# ESP32S3.net
KiCad netlist of a schematic drawn in Altium Designer
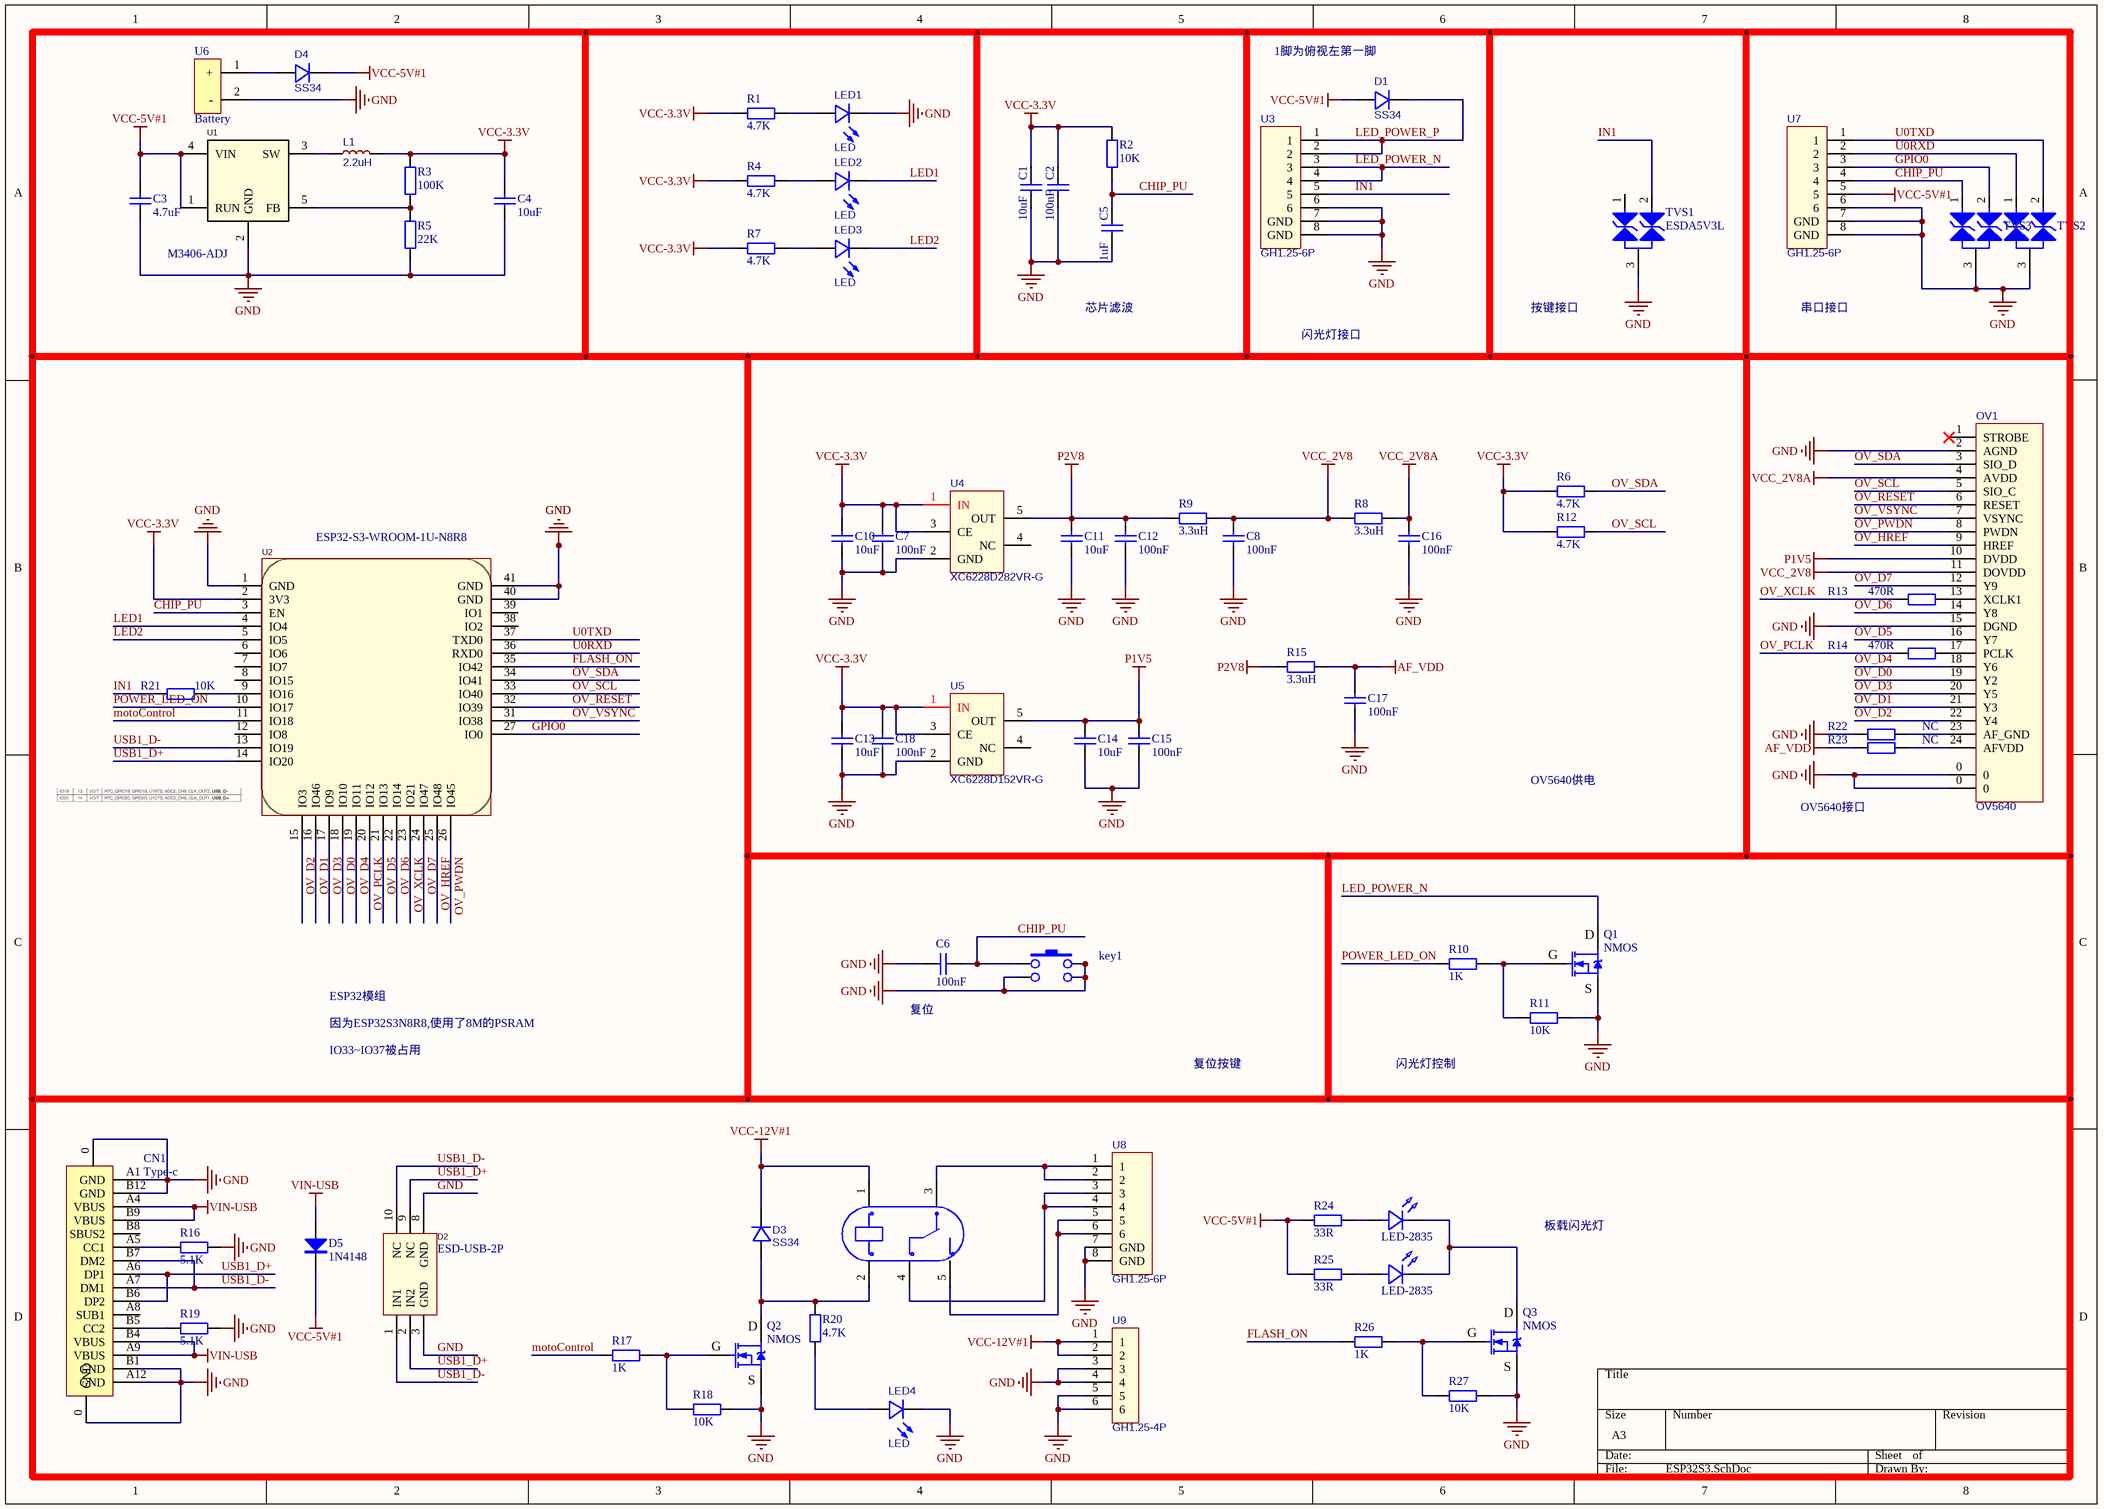
[diagram p0: ESP32S3.SchDoc]

(export (version "E")
  (design (tool "Eeschema 10.0.6"))
  (components
    (comp (ref "C1")
      (value "10uF")
      (footprint "0603-C")
      (description "贴片电容")
      (libsource (lib "封装库") (part "C"))
    )
    (comp (ref "C2")
      (value "100nF")
      (footprint "0603-C")
      (description "贴片电容")
      (libsource (lib "封装库") (part "C"))
    )
    (comp (ref "C3")
      (value "4.7uF")
      (footprint "0603-C")
      (description "贴片电容")
      (libsource (lib "封装库") (part "C"))
    )
    (comp (ref "C4")
      (value "10uF")
      (footprint "0603-C")
      (description "贴片电容")
      (libsource (lib "封装库") (part "C"))
    )
    (comp (ref "C5")
      (value "1uF")
      (footprint "0603-C")
      (description "贴片电容")
      (libsource (lib "封装库") (part "C"))
    )
    (comp (ref "C6")
      (value "100nF")
      (footprint "0603-C")
      (description "贴片电容")
      (libsource (lib "封装库") (part "C"))
    )
    (comp (ref "C7")
      (value "100nF")
      (footprint "0603-C")
      (description "贴片电容")
      (libsource (lib "封装库") (part "C"))
    )
    (comp (ref "C8")
      (value "100nF")
      (footprint "0603-C")
      (description "贴片电容")
      (libsource (lib "封装库") (part "C"))
    )
    (comp (ref "C10")
      (value "10uF")
      (footprint "0603-C")
      (description "贴片电容")
      (libsource (lib "封装库") (part "C"))
    )
    (comp (ref "C11")
      (value "10uF")
      (footprint "0603-C")
      (description "贴片电容")
      (libsource (lib "封装库") (part "C"))
    )
    (comp (ref "C12")
      (value "100nF")
      (footprint "0603-C")
      (description "贴片电容")
      (libsource (lib "封装库") (part "C"))
    )
    (comp (ref "C13")
      (value "10uF")
      (footprint "0603-C")
      (description "贴片电容")
      (libsource (lib "封装库") (part "C"))
    )
    (comp (ref "C14")
      (value "10uF")
      (footprint "0603-C")
      (description "贴片电容")
      (libsource (lib "封装库") (part "C"))
    )
    (comp (ref "C15")
      (value "100nF")
      (footprint "0603-C")
      (description "贴片电容")
      (libsource (lib "封装库") (part "C"))
    )
    (comp (ref "C16")
      (value "100nF")
      (footprint "0603-C")
      (description "贴片电容")
      (libsource (lib "封装库") (part "C"))
    )
    (comp (ref "C17")
      (value "100nF")
      (footprint "0603-C")
      (description "贴片电容")
      (libsource (lib "封装库") (part "C"))
    )
    (comp (ref "C18")
      (value "100nF")
      (footprint "0603-C")
      (description "贴片电容")
      (libsource (lib "封装库") (part "C"))
    )
    (comp (ref "CN1")
      (value "Type-c")
      (footprint "Type-c 16pin")
      (description "U262-161N-4BVC11")
      (libsource (lib "封装") (part "Type-c"))
    )
    (comp (ref "D1")
      (value "SS34")
      (footprint "SS34-SMA")
      (fields
        (field (name "BOM_SUPPLIER PART") "C118334")
        (field (name "BOM_MANUFACTURER PART") "D-G060306G1-KS2")
        (field (name "CONTRIBUTOR") "LCSC")
      )
      (libsource (lib "封装库") (part "SS34"))
    )
    (comp (ref "D2")
      (value "ESD-USB-2P")
      (footprint "SLP2510P8-2P")
      (description "RClamp0522PATCT")
      (fields (field (name "MANUFACTURER") "SEMTECH") (field (name "MANUFACTURER PART") "RClamp0524PATCT"))
      (libsource (lib "封装库") (part "ESD-USB-2P"))
    )
    (comp (ref "D3")
      (value "SS34")
      (footprint "SS34-SMA")
      (fields
        (field (name "BOM_SUPPLIER PART") "C118334")
        (field (name "BOM_MANUFACTURER PART") "D-G060306G1-KS2")
        (field (name "CONTRIBUTOR") "LCSC")
      )
      (libsource (lib "封装库") (part "SS34"))
    )
    (comp (ref "D4")
      (value "SS34")
      (footprint "SS34-SMA")
      (fields
        (field (name "BOM_SUPPLIER PART") "C118334")
        (field (name "BOM_MANUFACTURER PART") "D-G060306G1-KS2")
        (field (name "CONTRIBUTOR") "LCSC")
      )
      (libsource (lib "封装库") (part "SS34"))
    )
    (comp (ref "D5")
      (value "1N4148")
      (footprint "1N4148W")
      (description "整流二极管")
      (fields (field (name "版权归属") "源创客"))
      (libsource (lib "封装库") (part "1N4148W"))
    )
    (comp (ref "K1")
      (value "JQC-3FF/005-1ZS(551)")
      (footprint "RELAY-TH_HF3FF-XX-1ZXX-XXX")
      (fields (field (name "MANUFACTURER") "HF(宏发)"))
      (libsource (lib "封装库") (part "JQC-3FF/005-1ZS(551)"))
    )
    (comp (ref "key1") (value "KEY") (footprint "轻触开关侧按3*6*3.5") (libsource (lib "封装库") (part "轻触开关3*6*3.6")))
    (comp (ref "L1")
      (value "2.2uH")
      (footprint "电感 4.2X4.4")
      (description "L")
      (fields
        (field (name "BOM_MANUFACTURER PART") "UPZ2012D800-4R0TF")
        (field (name "BOM_SUPPLIER PART") "C145060")
        (field (name "CONTRIBUTOR") "LCSC")
      )
      (libsource (lib "封装库") (part "L"))
    )
    (comp (ref "LED1")
      (value "LED")
      (footprint "LED-0603")
      (fields
        (field (name "BOM_SUPPLIER PART") "C118334")
        (field (name "BOM_MANUFACTURER PART") "D-G060306G1-KS2")
        (field (name "CONTRIBUTOR") "LCSC")
      )
      (libsource (lib "封装库") (part "LED"))
    )
    (comp (ref "LED2")
      (value "LED")
      (footprint "LED-0603")
      (fields
        (field (name "BOM_SUPPLIER PART") "C118334")
        (field (name "BOM_MANUFACTURER PART") "D-G060306G1-KS2")
        (field (name "CONTRIBUTOR") "LCSC")
      )
      (libsource (lib "封装库") (part "LED"))
    )
    (comp (ref "LED3")
      (value "LED")
      (footprint "LED-0603")
      (fields
        (field (name "BOM_SUPPLIER PART") "C118334")
        (field (name "BOM_MANUFACTURER PART") "D-G060306G1-KS2")
        (field (name "CONTRIBUTOR") "LCSC")
      )
      (libsource (lib "封装库") (part "LED"))
    )
    (comp (ref "LED4")
      (value "LED")
      (footprint "LED-0603")
      (fields
        (field (name "BOM_SUPPLIER PART") "C118334")
        (field (name "BOM_MANUFACTURER PART") "D-G060306G1-KS2")
        (field (name "CONTRIBUTOR") "LCSC")
      )
      (libsource (lib "封装库") (part "LED"))
    )
    (comp (ref "OV1")
      (value "OV5640")
      (footprint "FPC-SMD_P0.50-24P_XJ-FGS")
      (fields (field (name "BOM_SUPPLIER PART") "C132514") (field (name "CONTRIBUTOR") "LCSC"))
      (libsource (lib "封装库") (part "OV5640"))
    )
    (comp (ref "Q1")
      (value "NMOS")
      (footprint "AO3400")
      (description "N沟道 30V/4.2A")
      (libsource (lib "封装库") (part "AO3400"))
    )
    (comp (ref "Q2")
      (value "NMOS")
      (footprint "AO3400")
      (description "N沟道 30V/4.2A")
      (libsource (lib "封装库") (part "AO3400"))
    )
    (comp (ref "Q3")
      (value "NMOS")
      (footprint "AO3400")
      (description "N沟道 30V/4.2A")
      (libsource (lib "封装库") (part "AO3400"))
    )
    (comp (ref "R1")
      (value "4.7K")
      (footprint "0603-R")
      (description "贴片电阻")
      (libsource (lib "封装库") (part "R"))
    )
    (comp (ref "R2")
      (value "10K")
      (footprint "0603-R")
      (description "贴片电阻")
      (libsource (lib "封装库") (part "R"))
    )
    (comp (ref "R3")
      (value "100K")
      (footprint "0603-R")
      (description "贴片电阻")
      (libsource (lib "封装库") (part "R"))
    )
    (comp (ref "R4")
      (value "4.7K")
      (footprint "0603-R")
      (description "贴片电阻")
      (libsource (lib "封装库") (part "R"))
    )
    (comp (ref "R5")
      (value "22K")
      (footprint "0603-R")
      (description "贴片电阻")
      (libsource (lib "封装库") (part "R"))
    )
    (comp (ref "R6")
      (value "4.7K")
      (footprint "0603-R")
      (description "贴片电阻")
      (libsource (lib "封装库") (part "R"))
    )
    (comp (ref "R7")
      (value "4.7K")
      (footprint "0603-R")
      (description "贴片电阻")
      (libsource (lib "封装库") (part "R"))
    )
    (comp (ref "R8")
      (value "3.3uH")
      (footprint "0603-R")
      (description "贴片电阻")
      (libsource (lib "封装库") (part "R"))
    )
    (comp (ref "R9")
      (value "3.3uH")
      (footprint "0603-R")
      (description "贴片电阻")
      (libsource (lib "封装库") (part "R"))
    )
    (comp (ref "R10")
      (value "1K")
      (footprint "0603-R")
      (description "贴片电阻")
      (libsource (lib "封装库") (part "R"))
    )
    (comp (ref "R11")
      (value "10K")
      (footprint "0603-R")
      (description "贴片电阻")
      (libsource (lib "封装库") (part "R"))
    )
    (comp (ref "R12")
      (value "4.7K")
      (footprint "0603-R")
      (description "贴片电阻")
      (libsource (lib "封装库") (part "R"))
    )
    (comp (ref "R13")
      (value "470R")
      (footprint "0603-R")
      (description "贴片电阻")
      (libsource (lib "封装库") (part "R"))
    )
    (comp (ref "R14")
      (value "470R")
      (footprint "0603-R")
      (description "贴片电阻")
      (libsource (lib "封装库") (part "R"))
    )
    (comp (ref "R15")
      (value "3.3uH")
      (footprint "0603-R")
      (description "贴片电阻")
      (libsource (lib "封装库") (part "R"))
    )
    (comp (ref "R16")
      (value "5.1K")
      (footprint "0603-R")
      (description "贴片电阻")
      (libsource (lib "封装库") (part "R"))
    )
    (comp (ref "R17")
      (value "1K")
      (footprint "0603-R")
      (description "贴片电阻")
      (libsource (lib "封装库") (part "R"))
    )
    (comp (ref "R18")
      (value "10K")
      (footprint "0603-R")
      (description "贴片电阻")
      (libsource (lib "封装库") (part "R"))
    )
    (comp (ref "R19")
      (value "5.1K")
      (footprint "0603-R")
      (description "贴片电阻")
      (libsource (lib "封装库") (part "R"))
    )
    (comp (ref "R20")
      (value "4.7K")
      (footprint "0603-R")
      (description "贴片电阻")
      (libsource (lib "封装库") (part "R"))
    )
    (comp (ref "R21")
      (value "10K")
      (footprint "0603-R")
      (description "贴片电阻")
      (libsource (lib "封装库") (part "R"))
    )
    (comp (ref "R22")
      (value "NC")
      (footprint "0603-R")
      (description "贴片电阻")
      (libsource (lib "封装库") (part "R"))
    )
    (comp (ref "R23")
      (value "NC")
      (footprint "0603-R")
      (description "贴片电阻")
      (libsource (lib "封装库") (part "R"))
    )
    (comp (ref "R24")
      (value "33R")
      (footprint "1206-R")
      (description "贴片电阻")
      (libsource (lib "封装库") (part "R"))
    )
    (comp (ref "R25")
      (value "33R")
      (footprint "1206-R")
      (description "贴片电阻")
      (libsource (lib "封装库") (part "R"))
    )
    (comp (ref "R26")
      (value "1K")
      (footprint "0603-R")
      (description "贴片电阻")
      (libsource (lib "封装库") (part "R"))
    )
    (comp (ref "R27")
      (value "10K")
      (footprint "0603-R")
      (description "贴片电阻")
      (libsource (lib "封装库") (part "R"))
    )
    (comp (ref "TVS1") (value "ESDA5V3L") (footprint "ESDA5V3L") (libsource (lib "封装库") (part "ESDA5V3L")))
    (comp (ref "TVS2") (value "ESDA5V3L") (footprint "ESDA5V3L") (libsource (lib "封装库") (part "ESDA5V3L")))
    (comp (ref "TVS3") (value "ESDA5V3L") (footprint "ESDA5V3L") (libsource (lib "封装库") (part "ESDA5V3L")))
    (comp (ref "U1")
      (value "M3406-ADJ")
      (footprint "M3406-ADJ")
      (fields (field (name "MANUFACTURER") "西安航天民芯"))
      (libsource (lib "封装库") (part "M3406-ADJ"))
    )
    (comp (ref "U2")
      (value "ESP32-S3-WROOM-1U-N8R8")
      (footprint "WIRELM-SMD_ESP32-S3-WROOM-1U")
      (fields
        (field (name "MANUFACTURER") "ESPRESSIF(乐鑫)")
        (field (name "MANUFACTURER PART") "ESP32-S3-WROOM-1U-N8")
      )
      (libsource (lib "封装库") (part "ESP32-S3-WROOM-1U-N8R8"))
    )
    (comp (ref "U3")
      (value "GH1.25-6P")
      (footprint "CONN-SMD_A1257WR-S-6P")
      (description "GH1.25-4PWBPZ")
      (fields (field (name "BOM_SUPPLIER PART") "C2829253") (field (name "CONTRIBUTOR") "LCSC"))
      (libsource (lib "封装库") (part "GH1.25-6P"))
    )
    (comp (ref "U4")
      (value "XC6228D282VR-G")
      (footprint "XC6228D332VR-G")
      (fields
        (field (name "BOM_MANUFACTURER PART") "XC6228D332VR-G")
        (field (name "BOM_SUPPLIER PART") "C69841")
      )
      (libsource (lib "封装库") (part "XC6228D282VR-G"))
    )
    (comp (ref "U5")
      (value "XC6228D152VR-G")
      (footprint "XC6228D332VR-G")
      (fields
        (field (name "BOM_MANUFACTURER PART") "XC6228D332VR-G")
        (field (name "BOM_SUPPLIER PART") "C69841")
      )
      (libsource (lib "封装库") (part "XC6228D282VR-G"))
    )
    (comp (ref "U6") (value "Battery") (footprint "锂电池焊盘") (libsource (lib "封装库") (part "Battery")))
    (comp (ref "U7")
      (value "GH1.25-6P")
      (footprint "CONN-SMD_A1257WR-S-6P")
      (description "GH1.25-4PWBPZ")
      (fields (field (name "BOM_SUPPLIER PART") "C2829253") (field (name "CONTRIBUTOR") "LCSC"))
      (libsource (lib "封装库") (part "GH1.25-6P"))
    )
    (comp (ref "U8")
      (value "GH1.25-6P")
      (footprint "CONN-SMD_A1257WR-S-6P")
      (description "GH1.25-4PWBPZ")
      (fields (field (name "BOM_SUPPLIER PART") "C2829253") (field (name "CONTRIBUTOR") "LCSC"))
      (libsource (lib "") (part "GH1.25-6P_1"))
    )
    (comp (ref "U9")
      (value "GH1.25-4P")
      (footprint "CONN-SMD_GH1.25-4PWBPZ")
      (description "GH1.25-4PWBPZ")
      (fields (field (name "BOM_SUPPLIER PART") "C2829253") (field (name "CONTRIBUTOR") "LCSC"))
      (libsource (lib "封装库") (part "GH1.25-4P"))
    )
    (comp (ref "U10")
      (value "LED-2835")
      (footprint "LED-SMD_L3.5-W2.8-FD-2835_WHITE")
      (fields
        (field (name "MANUFACTURER") "HONGLITRONIC(鸿利光电)")
        (field (name "MANUFACTURER PART") "A2835W3H2-D01-8D2AB5")
      )
      (libsource (lib "封装库") (part "LED-2835"))
    )
    (comp (ref "U11")
      (value "LED-2835")
      (footprint "LED-SMD_L3.5-W2.8-FD-2835_WHITE")
      (fields
        (field (name "MANUFACTURER") "HONGLITRONIC(鸿利光电)")
        (field (name "MANUFACTURER PART") "A2835W3H2-D01-8D2AB5")
      )
      (libsource (lib "封装库") (part "LED-2835"))
    )
  )
  (nets
    (net (code "1") (name "/CHIP_PU") (class "Default")
      (node (ref "C5") (pin "1") (pinfunction "1_1") (pintype "passive"))
      (node (ref "C6") (pin "1") (pinfunction "1_1") (pintype "passive"))
      (node (ref "R2") (pin "1") (pinfunction "1_1") (pintype "passive"))
      (node (ref "TVS3") (pin "1") (pinfunction "K_1") (pintype "passive"))
      (node (ref "U2") (pin "3") (pinfunction "EN_3") (pintype "passive"))
      (node (ref "U7") (pin "4") (pinfunction "4_4") (pintype "passive"))
      (node (ref "key1") (pin "1") (pinfunction "1_1") (pintype "passive"))
    )
    (net (code "2") (name "/FLASH_ON") (class "Default")
      (node (ref "R26") (pin "2") (pinfunction "2_2") (pintype "passive"))
      (node (ref "U2") (pin "35") (pinfunction "IO42_35") (pintype "passive"))
    )
    (net (code "3") (name "/GPIO0") (class "Default")
      (node (ref "TVS3") (pin "2") (pinfunction "A_2") (pintype "passive"))
      (node (ref "U2") (pin "27") (pinfunction "IO0_27") (pintype "passive"))
      (node (ref "U7") (pin "3") (pinfunction "3_3") (pintype "passive"))
    )
    (net (code "4") (name "/IN1") (class "Default")
      (node (ref "R21") (pin "2") (pinfunction "2_2") (pintype "passive"))
      (node (ref "TVS1") (pin "2") (pinfunction "A_2") (pintype "passive"))
      (node (ref "U3") (pin "5") (pinfunction "5_5") (pintype "passive"))
    )
    (net (code "5") (name "/LED1") (class "Default")
      (node (ref "LED2") (pin "1") (pinfunction "-_1") (pintype "passive"))
      (node (ref "U2") (pin "4") (pinfunction "IO4_4") (pintype "passive"))
    )
    (net (code "6") (name "/LED2") (class "Default")
      (node (ref "LED3") (pin "1") (pinfunction "-_1") (pintype "passive"))
      (node (ref "U2") (pin "5") (pinfunction "IO5_5") (pintype "passive"))
    )
    (net (code "7") (name "/LED_POWER_N") (class "Default")
      (node (ref "Q1") (pin "3") (pinfunction "D_3") (pintype "passive"))
      (node (ref "U3") (pin "3") (pinfunction "3_3") (pintype "passive"))
      (node (ref "U3") (pin "4") (pinfunction "4_4") (pintype "passive"))
    )
    (net (code "8") (name "/LED_POWER_P") (class "Default")
      (node (ref "D1") (pin "2") (pinfunction "-_2") (pintype "passive"))
      (node (ref "U3") (pin "1") (pinfunction "1_1") (pintype "passive"))
      (node (ref "U3") (pin "2") (pinfunction "2_2") (pintype "passive"))
    )
    (net (code "9") (name "/OV_D0") (class "Default")
      (node (ref "OV1") (pin "19") (pinfunction "Y2_19") (pintype "passive"))
      (node (ref "U2") (pin "18") (pinfunction "IO10_18") (pintype "passive"))
    )
    (net (code "10") (name "/OV_D1") (class "Default")
      (node (ref "OV1") (pin "21") (pinfunction "Y3_21") (pintype "passive"))
      (node (ref "U2") (pin "16") (pinfunction "IO46_16") (pintype "passive"))
    )
    (net (code "11") (name "/OV_D2") (class "Default")
      (node (ref "OV1") (pin "22") (pinfunction "Y4_22") (pintype "passive"))
      (node (ref "U2") (pin "15") (pinfunction "IO3_15") (pintype "passive"))
    )
    (net (code "12") (name "/OV_D3") (class "Default")
      (node (ref "OV1") (pin "20") (pinfunction "Y5_20") (pintype "passive"))
      (node (ref "U2") (pin "17") (pinfunction "IO9_17") (pintype "passive"))
    )
    (net (code "13") (name "/OV_D4") (class "Default")
      (node (ref "OV1") (pin "18") (pinfunction "Y6_18") (pintype "passive"))
      (node (ref "U2") (pin "19") (pinfunction "IO11_19") (pintype "passive"))
    )
    (net (code "14") (name "/OV_D5") (class "Default")
      (node (ref "OV1") (pin "16") (pinfunction "Y7_16") (pintype "passive"))
      (node (ref "U2") (pin "21") (pinfunction "IO13_21") (pintype "passive"))
    )
    (net (code "15") (name "/OV_D6") (class "Default")
      (node (ref "OV1") (pin "14") (pinfunction "Y8_14") (pintype "passive"))
      (node (ref "U2") (pin "22") (pinfunction "IO14_22") (pintype "passive"))
    )
    (net (code "16") (name "/OV_D7") (class "Default")
      (node (ref "OV1") (pin "12") (pinfunction "Y9_12") (pintype "passive"))
      (node (ref "U2") (pin "24") (pinfunction "IO47_24") (pintype "passive"))
    )
    (net (code "17") (name "/OV_HREF") (class "Default")
      (node (ref "OV1") (pin "9") (pinfunction "HREF_9") (pintype "passive"))
      (node (ref "U2") (pin "25") (pinfunction "IO48_25") (pintype "passive"))
    )
    (net (code "18") (name "/OV_PCLK") (class "Default")
      (node (ref "R14") (pin "2") (pinfunction "2_2") (pintype "passive"))
      (node (ref "U2") (pin "20") (pinfunction "IO12_20") (pintype "passive"))
    )
    (net (code "19") (name "/OV_PWDN") (class "Default")
      (node (ref "OV1") (pin "8") (pinfunction "PWDN_8") (pintype "passive"))
      (node (ref "U2") (pin "26") (pinfunction "IO45_26") (pintype "passive"))
    )
    (net (code "20") (name "/OV_RESET") (class "Default")
      (node (ref "OV1") (pin "6") (pinfunction "RESET_6") (pintype "passive"))
      (node (ref "U2") (pin "32") (pinfunction "IO39_32") (pintype "passive"))
    )
    (net (code "21") (name "/OV_SCL") (class "Default")
      (node (ref "OV1") (pin "5") (pinfunction "SIO_C_5") (pintype "passive"))
      (node (ref "R12") (pin "1") (pinfunction "1_1") (pintype "passive"))
      (node (ref "U2") (pin "33") (pinfunction "IO40_33") (pintype "passive"))
    )
    (net (code "22") (name "/OV_SDA") (class "Default")
      (node (ref "OV1") (pin "3") (pinfunction "SIO_D_3") (pintype "passive"))
      (node (ref "R6") (pin "1") (pinfunction "1_1") (pintype "passive"))
      (node (ref "U2") (pin "34") (pinfunction "IO41_34") (pintype "passive"))
    )
    (net (code "23") (name "/OV_VSYNC") (class "Default")
      (node (ref "OV1") (pin "7") (pinfunction "VSYNC_7") (pintype "passive"))
      (node (ref "U2") (pin "31") (pinfunction "IO38_31") (pintype "passive"))
    )
    (net (code "24") (name "/OV_XCLK") (class "Default")
      (node (ref "R13") (pin "2") (pinfunction "2_2") (pintype "passive"))
      (node (ref "U2") (pin "23") (pinfunction "IO21_23") (pintype "passive"))
    )
    (net (code "25") (name "/POWER_LED_ON") (class "Default")
      (node (ref "R10") (pin "2") (pinfunction "2_2") (pintype "passive"))
      (node (ref "U2") (pin "10") (pinfunction "IO17_10") (pintype "passive"))
    )
    (net (code "26") (name "/U0RXD") (class "Default")
      (node (ref "TVS2") (pin "1") (pinfunction "K_1") (pintype "passive"))
      (node (ref "U2") (pin "36") (pinfunction "RXD0_36") (pintype "passive"))
      (node (ref "U7") (pin "2") (pinfunction "2_2") (pintype "passive"))
    )
    (net (code "27") (name "/U0TXD") (class "Default")
      (node (ref "TVS2") (pin "2") (pinfunction "A_2") (pintype "passive"))
      (node (ref "U2") (pin "37") (pinfunction "TXD0_37") (pintype "passive"))
      (node (ref "U7") (pin "1") (pinfunction "1_1") (pintype "passive"))
    )
    (net (code "28") (name "/USB1_D+") (class "Default")
      (node (ref "CN1") (pin "A6") (pinfunction "DP1_A6") (pintype "passive"))
      (node (ref "CN1") (pin "B6") (pinfunction "DP2_B6") (pintype "passive"))
      (node (ref "D2") (pin "2") (pinfunction "IN2_2") (pintype "passive"))
      (node (ref "D2") (pin "9") (pinfunction "NC_9") (pintype "passive"))
      (node (ref "U2") (pin "14") (pinfunction "IO20_14") (pintype "passive"))
    )
    (net (code "29") (name "/USB1_D-") (class "Default")
      (node (ref "CN1") (pin "A7") (pinfunction "DM1_A7") (pintype "passive"))
      (node (ref "CN1") (pin "B7") (pinfunction "DM2_B7") (pintype "passive"))
      (node (ref "D2") (pin "1") (pinfunction "IN1_1") (pintype "passive"))
      (node (ref "D2") (pin "10") (pinfunction "NC_10") (pintype "passive"))
      (node (ref "U2") (pin "13") (pinfunction "IO19_13") (pintype "passive"))
    )
    (net (code "30") (name "/motoControl") (class "Default")
      (node (ref "R17") (pin "2") (pinfunction "2_2") (pintype "passive"))
      (node (ref "U2") (pin "11") (pinfunction "IO18_11") (pintype "passive"))
    )
    (net (code "31") (name "AF_VDD") (class "Default")
      (node (ref "C17") (pin "2") (pinfunction "2_2") (pintype "passive"))
      (node (ref "R15") (pin "2") (pinfunction "2_2") (pintype "passive"))
      (node (ref "R23") (pin "2") (pinfunction "2_2") (pintype "passive"))
    )
    (net (code "32") (name "GND") (class "Default")
      (node (ref "C1") (pin "1") (pinfunction "1_1") (pintype "passive"))
      (node (ref "C10") (pin "1") (pinfunction "1_1") (pintype "passive"))
      (node (ref "C11") (pin "1") (pinfunction "1_1") (pintype "passive"))
      (node (ref "C12") (pin "1") (pinfunction "1_1") (pintype "passive"))
      (node (ref "C13") (pin "1") (pinfunction "1_1") (pintype "passive"))
      (node (ref "C14") (pin "1") (pinfunction "1_1") (pintype "passive"))
      (node (ref "C15") (pin "1") (pinfunction "1_1") (pintype "passive"))
      (node (ref "C16") (pin "1") (pinfunction "1_1") (pintype "passive"))
      (node (ref "C17") (pin "1") (pinfunction "1_1") (pintype "passive"))
      (node (ref "C18") (pin "1") (pinfunction "1_1") (pintype "passive"))
      (node (ref "C2") (pin "2") (pinfunction "2_2") (pintype "passive"))
      (node (ref "C3") (pin "1") (pinfunction "1_1") (pintype "passive"))
      (node (ref "C4") (pin "1") (pinfunction "1_1") (pintype "passive"))
      (node (ref "C5") (pin "2") (pinfunction "2_2") (pintype "passive"))
      (node (ref "C6") (pin "2") (pinfunction "2_2") (pintype "passive"))
      (node (ref "C7") (pin "1") (pinfunction "1_1") (pintype "passive"))
      (node (ref "C8") (pin "1") (pinfunction "1_1") (pintype "passive"))
      (node (ref "CN1") (pin "0") (pinfunction "GND_0") (pintype "passive"))
      (node (ref "CN1") (pin "A1") (pinfunction "GND_A1") (pintype "passive"))
      (node (ref "CN1") (pin "A12") (pinfunction "GND_A12") (pintype "passive"))
      (node (ref "CN1") (pin "B1") (pinfunction "GND_B1") (pintype "passive"))
      (node (ref "CN1") (pin "B12") (pinfunction "GND_B12") (pintype "passive"))
      (node (ref "D2") (pin "3") (pinfunction "GND_3") (pintype "passive"))
      (node (ref "D2") (pin "8") (pinfunction "GND_8") (pintype "passive"))
      (node (ref "LED1") (pin "1") (pinfunction "-_1") (pintype "passive"))
      (node (ref "LED4") (pin "1") (pinfunction "-_1") (pintype "passive"))
      (node (ref "OV1") (pin "0") (pinfunction "0_0") (pintype "passive"))
      (node (ref "OV1") (pin "15") (pinfunction "DGND_15") (pintype "passive"))
      (node (ref "OV1") (pin "2") (pinfunction "AGND_2") (pintype "passive"))
      (node (ref "Q1") (pin "2") (pinfunction "S_2") (pintype "passive"))
      (node (ref "Q2") (pin "2") (pinfunction "S_2") (pintype "passive"))
      (node (ref "Q3") (pin "2") (pinfunction "S_2") (pintype "passive"))
      (node (ref "R11") (pin "1") (pinfunction "1_1") (pintype "passive"))
      (node (ref "R16") (pin "2") (pinfunction "2_2") (pintype "passive"))
      (node (ref "R18") (pin "1") (pinfunction "1_1") (pintype "passive"))
      (node (ref "R19") (pin "2") (pinfunction "2_2") (pintype "passive"))
      (node (ref "R22") (pin "2") (pinfunction "2_2") (pintype "passive"))
      (node (ref "R27") (pin "1") (pinfunction "1_1") (pintype "passive"))
      (node (ref "R5") (pin "2") (pinfunction "2_2") (pintype "passive"))
      (node (ref "TVS1") (pin "3") (pinfunction "K_3") (pintype "passive"))
      (node (ref "TVS2") (pin "3") (pinfunction "K_3") (pintype "passive"))
      (node (ref "TVS3") (pin "3") (pinfunction "K_3") (pintype "passive"))
      (node (ref "U1") (pin "2") (pinfunction "GND_2") (pintype "passive"))
      (node (ref "U2") (pin "1") (pinfunction "GND_1") (pintype "passive"))
      (node (ref "U2") (pin "40") (pinfunction "GND_40") (pintype "passive"))
      (node (ref "U2") (pin "41") (pinfunction "GND_41") (pintype "passive"))
      (node (ref "U3") (pin "6") (pinfunction "6_6") (pintype "passive"))
      (node (ref "U3") (pin "7") (pinfunction "GND_7") (pintype "passive"))
      (node (ref "U3") (pin "8") (pinfunction "GND_8") (pintype "passive"))
      (node (ref "U4") (pin "2") (pinfunction "GND_2") (pintype "passive"))
      (node (ref "U5") (pin "2") (pinfunction "GND_2") (pintype "passive"))
      (node (ref "U6") (pin "2") (pinfunction "-_2") (pintype "passive"))
      (node (ref "U7") (pin "6") (pinfunction "6_6") (pintype "passive"))
      (node (ref "U7") (pin "7") (pinfunction "GND_7") (pintype "passive"))
      (node (ref "U7") (pin "8") (pinfunction "GND_8") (pintype "passive"))
      (node (ref "U8") (pin "7") (pinfunction "GND_7") (pintype "passive"))
      (node (ref "U8") (pin "8") (pinfunction "GND_8") (pintype "passive"))
      (node (ref "U9") (pin "3") (pinfunction "3_3") (pintype "passive"))
      (node (ref "U9") (pin "4") (pinfunction "4_4") (pintype "passive"))
      (node (ref "U9") (pin "5") (pinfunction "5_5") (pintype "passive"))
      (node (ref "U9") (pin "6") (pinfunction "6_6") (pintype "passive"))
      (node (ref "key1") (pin "2") (pinfunction "2_2") (pintype "passive"))
      (node (ref "key1") (pin "3") (pinfunction "3_3") (pintype "passive"))
      (node (ref "key1") (pin "4") (pinfunction "4_4") (pintype "passive"))
    )
    (net (code "33") (name "Net-(CN1-CC1)") (class "Default")
      (node (ref "CN1") (pin "A5") (pinfunction "CC1_A5") (pintype "passive"))
      (node (ref "R16") (pin "1") (pinfunction "1_1") (pintype "passive"))
    )
    (net (code "34") (name "Net-(CN1-CC2)") (class "Default")
      (node (ref "CN1") (pin "B5") (pinfunction "CC2_B5") (pintype "passive"))
      (node (ref "R19") (pin "1") (pinfunction "1_1") (pintype "passive"))
    )
    (net (code "35") (name "Net-(D3-+)") (class "Default")
      (node (ref "D3") (pin "1") (pinfunction "+_1") (pintype "passive"))
      (node (ref "K1") (pin "2") (pinfunction "2_2") (pintype "passive"))
      (node (ref "Q2") (pin "3") (pinfunction "D_3") (pintype "passive"))
      (node (ref "R20") (pin "1") (pinfunction "1_1") (pintype "passive"))
    )
    (net (code "36") (name "Net-(D4-+)") (class "Default")
      (node (ref "D4") (pin "1") (pinfunction "+_1") (pintype "passive"))
      (node (ref "U6") (pin "1") (pinfunction "+_1") (pintype "passive"))
    )
    (net (code "37") (name "Net-(K1-Pad3)") (class "Default")
      (node (ref "K1") (pin "3") (pinfunction "3_3") (pintype "passive"))
      (node (ref "U8") (pin "1") (pinfunction "1_1") (pintype "passive"))
      (node (ref "U8") (pin "2") (pinfunction "2_2") (pintype "passive"))
    )
    (net (code "38") (name "Net-(K1-Pad4)") (class "Default")
      (node (ref "K1") (pin "4") (pinfunction "4_4") (pintype "passive"))
      (node (ref "U8") (pin "3") (pinfunction "3_3") (pintype "passive"))
      (node (ref "U8") (pin "4") (pinfunction "4_4") (pintype "passive"))
    )
    (net (code "39") (name "Net-(K1-Pad5)") (class "Default")
      (node (ref "K1") (pin "5") (pinfunction "5_5") (pintype "passive"))
      (node (ref "U8") (pin "5") (pinfunction "5_5") (pintype "passive"))
      (node (ref "U8") (pin "6") (pinfunction "6_6") (pintype "passive"))
    )
    (net (code "40") (name "Net-(LED1-+)") (class "Default")
      (node (ref "LED1") (pin "2") (pinfunction "+_2") (pintype "passive"))
      (node (ref "R1") (pin "2") (pinfunction "2_2") (pintype "passive"))
    )
    (net (code "41") (name "Net-(LED2-+)") (class "Default")
      (node (ref "LED2") (pin "2") (pinfunction "+_2") (pintype "passive"))
      (node (ref "R4") (pin "2") (pinfunction "2_2") (pintype "passive"))
    )
    (net (code "42") (name "Net-(LED3-+)") (class "Default")
      (node (ref "LED3") (pin "2") (pinfunction "+_2") (pintype "passive"))
      (node (ref "R7") (pin "2") (pinfunction "2_2") (pintype "passive"))
    )
    (net (code "43") (name "Net-(LED4-+)") (class "Default")
      (node (ref "LED4") (pin "2") (pinfunction "+_2") (pintype "passive"))
      (node (ref "R20") (pin "2") (pinfunction "2_2") (pintype "passive"))
    )
    (net (code "44") (name "Net-(OV1-AFVDD)") (class "Default")
      (node (ref "OV1") (pin "24") (pinfunction "AFVDD_24") (pintype "passive"))
      (node (ref "R23") (pin "1") (pinfunction "1_1") (pintype "passive"))
    )
    (net (code "45") (name "Net-(OV1-AF_GND)") (class "Default")
      (node (ref "OV1") (pin "23") (pinfunction "AF_GND_23") (pintype "passive"))
      (node (ref "R22") (pin "1") (pinfunction "1_1") (pintype "passive"))
    )
    (net (code "46") (name "Net-(OV1-PCLK)") (class "Default")
      (node (ref "OV1") (pin "17") (pinfunction "PCLK_17") (pintype "passive"))
      (node (ref "R14") (pin "1") (pinfunction "1_1") (pintype "passive"))
    )
    (net (code "47") (name "Net-(OV1-XCLK1)") (class "Default")
      (node (ref "OV1") (pin "13") (pinfunction "XCLK1_13") (pintype "passive"))
      (node (ref "R13") (pin "1") (pinfunction "1_1") (pintype "passive"))
    )
    (net (code "48") (name "Net-(Q1-G)") (class "Default")
      (node (ref "Q1") (pin "1") (pinfunction "G_1") (pintype "passive"))
      (node (ref "R10") (pin "1") (pinfunction "1_1") (pintype "passive"))
      (node (ref "R11") (pin "2") (pinfunction "2_2") (pintype "passive"))
    )
    (net (code "49") (name "Net-(Q2-G)") (class "Default")
      (node (ref "Q2") (pin "1") (pinfunction "G_1") (pintype "passive"))
      (node (ref "R17") (pin "1") (pinfunction "1_1") (pintype "passive"))
      (node (ref "R18") (pin "2") (pinfunction "2_2") (pintype "passive"))
    )
    (net (code "50") (name "Net-(Q3-D)") (class "Default")
      (node (ref "Q3") (pin "3") (pinfunction "D_3") (pintype "passive"))
      (node (ref "U10") (pin "1") (pinfunction "K_1") (pintype "passive"))
      (node (ref "U11") (pin "1") (pinfunction "K_1") (pintype "passive"))
    )
    (net (code "51") (name "Net-(Q3-G)") (class "Default")
      (node (ref "Q3") (pin "1") (pinfunction "G_1") (pintype "passive"))
      (node (ref "R26") (pin "1") (pinfunction "1_1") (pintype "passive"))
      (node (ref "R27") (pin "2") (pinfunction "2_2") (pintype "passive"))
    )
    (net (code "52") (name "Net-(U1-FB)") (class "Default")
      (node (ref "R3") (pin "1") (pinfunction "1_1") (pintype "passive"))
      (node (ref "R5") (pin "1") (pinfunction "1_1") (pintype "passive"))
      (node (ref "U1") (pin "5") (pinfunction "FB_5") (pintype "passive"))
    )
    (net (code "53") (name "Net-(U1-SW)") (class "Default")
      (node (ref "L1") (pin "1") (pinfunction "1_1") (pintype "passive"))
      (node (ref "U1") (pin "3") (pinfunction "SW_3") (pintype "passive"))
    )
    (net (code "54") (name "Net-(U2-IO16)") (class "Default")
      (node (ref "R21") (pin "1") (pinfunction "1_1") (pintype "passive"))
      (node (ref "U2") (pin "9") (pinfunction "IO16_9") (pintype "passive"))
    )
    (net (code "55") (name "Net-(U10-A)") (class "Default")
      (node (ref "R24") (pin "1") (pinfunction "1_1") (pintype "passive"))
      (node (ref "U10") (pin "2") (pinfunction "A_2") (pintype "passive"))
    )
    (net (code "56") (name "Net-(U11-A)") (class "Default")
      (node (ref "R25") (pin "1") (pinfunction "1_1") (pintype "passive"))
      (node (ref "U11") (pin "2") (pinfunction "A_2") (pintype "passive"))
    )
    (net (code "57") (name "P1V5") (class "Default")
      (node (ref "C14") (pin "2") (pinfunction "2_2") (pintype "passive"))
      (node (ref "C15") (pin "2") (pinfunction "2_2") (pintype "passive"))
      (node (ref "OV1") (pin "10") (pinfunction "DVDD_10") (pintype "passive"))
      (node (ref "U5") (pin "5") (pinfunction "OUT_5") (pintype "passive"))
    )
    (net (code "58") (name "P2V8") (class "Default")
      (node (ref "C11") (pin "2") (pinfunction "2_2") (pintype "passive"))
      (node (ref "C12") (pin "2") (pinfunction "2_2") (pintype "passive"))
      (node (ref "R15") (pin "1") (pinfunction "1_1") (pintype "passive"))
      (node (ref "R9") (pin "1") (pinfunction "1_1") (pintype "passive"))
      (node (ref "U4") (pin "5") (pinfunction "OUT_5") (pintype "passive"))
    )
    (net (code "59") (name "VCC-3.3V") (class "Default")
      (node (ref "C1") (pin "2") (pinfunction "2_2") (pintype "passive"))
      (node (ref "C10") (pin "2") (pinfunction "2_2") (pintype "passive"))
      (node (ref "C13") (pin "2") (pinfunction "2_2") (pintype "passive"))
      (node (ref "C18") (pin "2") (pinfunction "2_2") (pintype "passive"))
      (node (ref "C2") (pin "1") (pinfunction "1_1") (pintype "passive"))
      (node (ref "C4") (pin "2") (pinfunction "2_2") (pintype "passive"))
      (node (ref "C7") (pin "2") (pinfunction "2_2") (pintype "passive"))
      (node (ref "L1") (pin "2") (pinfunction "2_2") (pintype "passive"))
      (node (ref "R1") (pin "1") (pinfunction "1_1") (pintype "passive"))
      (node (ref "R12") (pin "2") (pinfunction "2_2") (pintype "passive"))
      (node (ref "R2") (pin "2") (pinfunction "2_2") (pintype "passive"))
      (node (ref "R3") (pin "2") (pinfunction "2_2") (pintype "passive"))
      (node (ref "R4") (pin "1") (pinfunction "1_1") (pintype "passive"))
      (node (ref "R6") (pin "2") (pinfunction "2_2") (pintype "passive"))
      (node (ref "R7") (pin "1") (pinfunction "1_1") (pintype "passive"))
      (node (ref "U2") (pin "2") (pinfunction "3V3_2") (pintype "passive"))
      (node (ref "U4") (pin "1") (pinfunction "IN_1") (pintype "passive"))
      (node (ref "U4") (pin "3") (pinfunction "CE_3") (pintype "passive"))
      (node (ref "U5") (pin "1") (pinfunction "IN_1") (pintype "passive"))
      (node (ref "U5") (pin "3") (pinfunction "CE_3") (pintype "passive"))
    )
    (net (code "60") (name "VCC-5V#1") (class "Default")
      (node (ref "C3") (pin "2") (pinfunction "2_2") (pintype "passive"))
      (node (ref "D1") (pin "1") (pinfunction "+_1") (pintype "passive"))
      (node (ref "D4") (pin "2") (pinfunction "-_2") (pintype "passive"))
      (node (ref "D5") (pin "2") (pinfunction "K_2") (pintype "passive"))
      (node (ref "R24") (pin "2") (pinfunction "2_2") (pintype "passive"))
      (node (ref "R25") (pin "2") (pinfunction "2_2") (pintype "passive"))
      (node (ref "U1") (pin "1") (pinfunction "RUN_1") (pintype "passive"))
      (node (ref "U1") (pin "4") (pinfunction "VIN_4") (pintype "passive"))
      (node (ref "U7") (pin "5") (pinfunction "5_5") (pintype "passive"))
    )
    (net (code "61") (name "VCC-12V#1") (class "Default")
      (node (ref "D3") (pin "2") (pinfunction "-_2") (pintype "passive"))
      (node (ref "K1") (pin "1") (pinfunction "1_1") (pintype "passive"))
      (node (ref "U9") (pin "1") (pinfunction "1_1") (pintype "passive"))
      (node (ref "U9") (pin "2") (pinfunction "2_2") (pintype "passive"))
    )
    (net (code "62") (name "VCC_2V8") (class "Default")
      (node (ref "C8") (pin "2") (pinfunction "2_2") (pintype "passive"))
      (node (ref "OV1") (pin "11") (pinfunction "DOVDD_11") (pintype "passive"))
      (node (ref "R8") (pin "1") (pinfunction "1_1") (pintype "passive"))
      (node (ref "R9") (pin "2") (pinfunction "2_2") (pintype "passive"))
    )
    (net (code "63") (name "VCC_2V8A") (class "Default")
      (node (ref "C16") (pin "2") (pinfunction "2_2") (pintype "passive"))
      (node (ref "OV1") (pin "4") (pinfunction "AVDD_4") (pintype "passive"))
      (node (ref "R8") (pin "2") (pinfunction "2_2") (pintype "passive"))
    )
    (net (code "64") (name "VIN-USB") (class "Default")
      (node (ref "CN1") (pin "A4") (pinfunction "VBUS_A4") (pintype "passive"))
      (node (ref "CN1") (pin "A9") (pinfunction "VBUS_A9") (pintype "passive"))
      (node (ref "CN1") (pin "B4") (pinfunction "VBUS_B4") (pintype "passive"))
      (node (ref "CN1") (pin "B9") (pinfunction "VBUS_B9") (pintype "passive"))
      (node (ref "D5") (pin "1") (pinfunction "A_1") (pintype "passive"))
    )
    (net (code "65") (name "unconnected-(CN1-SBUS2-PadB8)") (class "Default")
      (node (ref "CN1") (pin "B8") (pinfunction "SBUS2_B8") (pintype "passive"))
    )
    (net (code "66") (name "unconnected-(CN1-SUB1-PadA8)") (class "Default")
      (node (ref "CN1") (pin "A8") (pinfunction "SUB1_A8") (pintype "passive"))
    )
    (net (code "67") (name "unconnected-(OV1-STROBE-Pad1)") (class "Default")
      (node (ref "OV1") (pin "1") (pinfunction "STROBE_1") (pintype "passive+no_connect"))
    )
    (net (code "68") (name "unconnected-(TVS1-K-Pad1)") (class "Default")
      (node (ref "TVS1") (pin "1") (pinfunction "K_1") (pintype "passive"))
    )
    (net (code "69") (name "unconnected-(U2-IO1-Pad39)") (class "Default")
      (node (ref "U2") (pin "39") (pinfunction "IO1_39") (pintype "passive"))
    )
    (net (code "70") (name "unconnected-(U2-IO2-Pad38)") (class "Default")
      (node (ref "U2") (pin "38") (pinfunction "IO2_38") (pintype "passive"))
    )
    (net (code "71") (name "unconnected-(U2-IO6-Pad6)") (class "Default")
      (node (ref "U2") (pin "6") (pinfunction "IO6_6") (pintype "passive"))
    )
    (net (code "72") (name "unconnected-(U2-IO7-Pad7)") (class "Default")
      (node (ref "U2") (pin "7") (pinfunction "IO7_7") (pintype "passive"))
    )
    (net (code "73") (name "unconnected-(U2-IO8-Pad12)") (class "Default")
      (node (ref "U2") (pin "12") (pinfunction "IO8_12") (pintype "passive"))
    )
    (net (code "74") (name "unconnected-(U2-IO15-Pad8)") (class "Default")
      (node (ref "U2") (pin "8") (pinfunction "IO15_8") (pintype "passive"))
    )
    (net (code "75") (name "unconnected-(U4-NC-Pad4)") (class "Default")
      (node (ref "U4") (pin "4") (pinfunction "NC_4") (pintype "passive"))
    )
    (net (code "76") (name "unconnected-(U5-NC-Pad4)") (class "Default")
      (node (ref "U5") (pin "4") (pinfunction "NC_4") (pintype "passive"))
    )
  )
)
